# design.net
KiCad netlist of a schematic drawn in Altium Designer
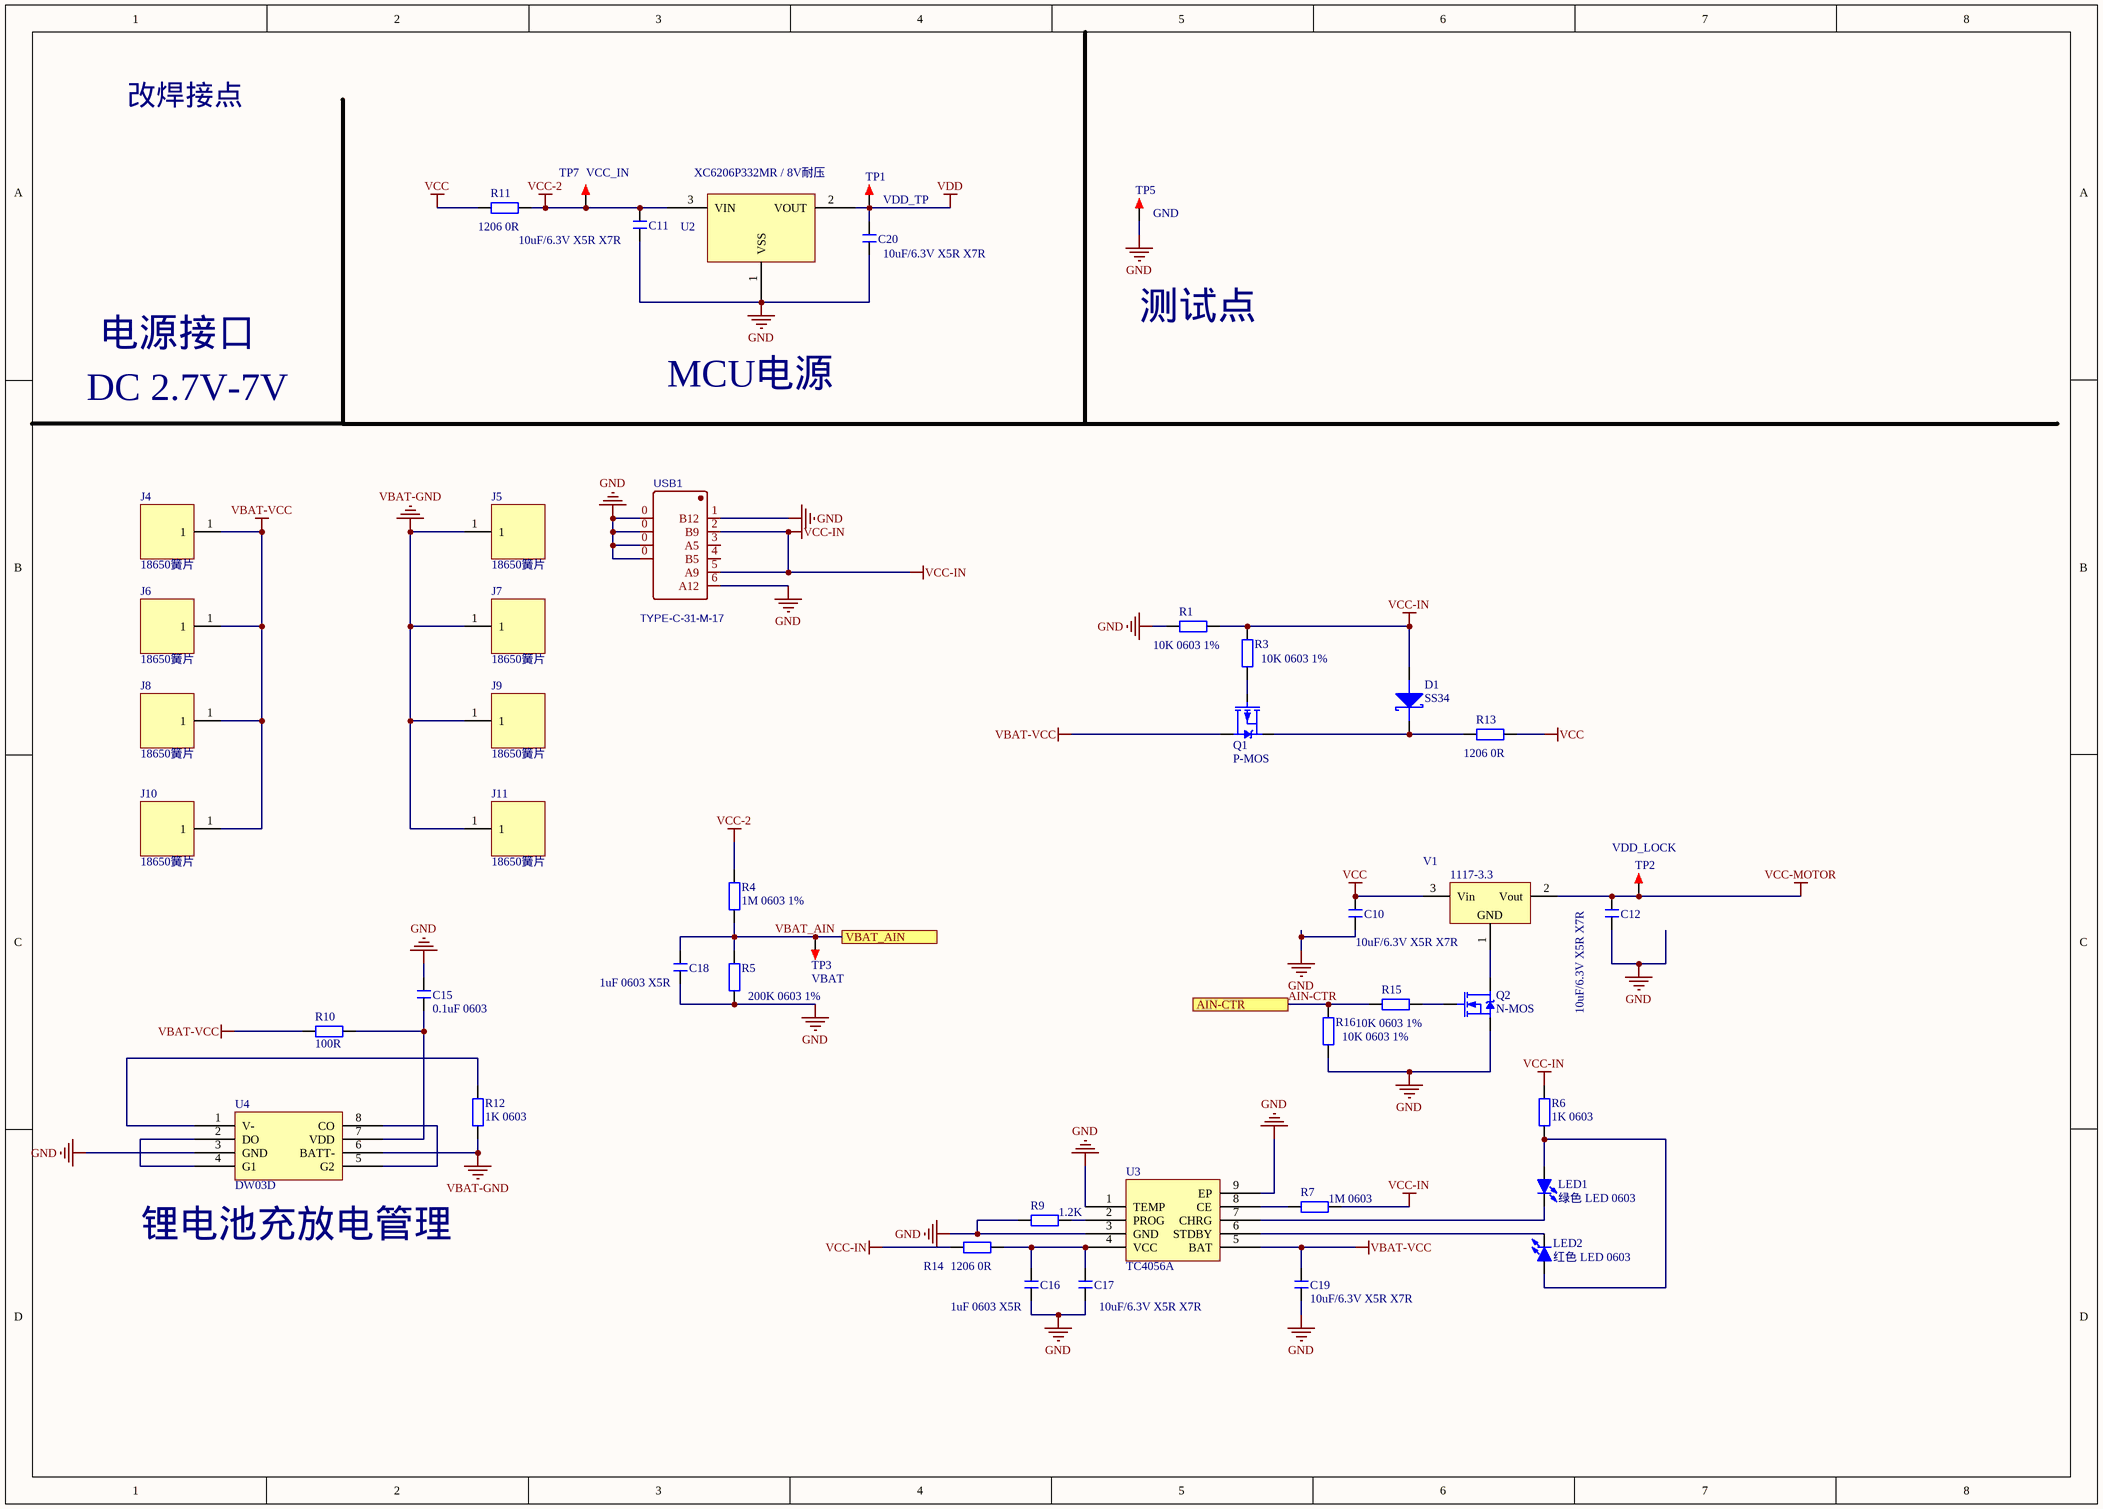
[diagram p0: 电源.SchDoc]

(export (version "E")
  (design (tool "Eeschema 10.0.6"))
  (components
    (comp (ref "C10")
      (value "10uF/6.3V X5R X7R")
      (footprint "C 0603")
      (description "无极性贴片电容")
      (fields (field (name "版权归属") "源创客"))
      (libsource (lib "源创客") (part "C"))
    )
    (comp (ref "C11")
      (value "10uF/6.3V X5R X7R")
      (footprint "C 0603")
      (description "无极性贴片电容")
      (fields (field (name "版权归属") "源创客"))
      (libsource (lib "源创客") (part "C"))
    )
    (comp (ref "C12")
      (value "10uF/6.3V X5R X7R")
      (footprint "C 0603")
      (description "无极性贴片电容")
      (fields (field (name "版权归属") "源创客"))
      (libsource (lib "源创客") (part "C"))
    )
    (comp (ref "C15")
      (value "0.1uF 0603")
      (footprint "C 0603")
      (description "无极性贴片电容")
      (fields (field (name "版权归属") "源创客"))
      (libsource (lib "源创客") (part "C"))
    )
    (comp (ref "C16")
      (value "1uF 0603 X5R")
      (footprint "C 0603")
      (description "无极性贴片电容")
      (fields (field (name "版权归属") "源创客"))
      (libsource (lib "源创客") (part "C"))
    )
    (comp (ref "C17")
      (value "10uF/6.3V X5R X7R")
      (footprint "C 0603")
      (description "无极性贴片电容")
      (fields (field (name "版权归属") "源创客"))
      (libsource (lib "源创客") (part "C"))
    )
    (comp (ref "C18")
      (value "1uF 0603 X5R")
      (footprint "C 0603")
      (description "无极性贴片电容")
      (fields (field (name "版权归属") "源创客"))
      (libsource (lib "源创客") (part "C"))
    )
    (comp (ref "C19")
      (value "10uF/6.3V X5R X7R")
      (footprint "C 0603")
      (description "无极性贴片电容")
      (fields (field (name "版权归属") "源创客"))
      (libsource (lib "源创客") (part "C"))
    )
    (comp (ref "C20")
      (value "10uF/6.3V X5R X7R")
      (footprint "C 0603")
      (description "无极性贴片电容")
      (fields (field (name "版权归属") "源创客"))
      (libsource (lib "源创客") (part "C"))
    )
    (comp (ref "D1")
      (value "SS34")
      (footprint "SMA/DO-214AC")
      (description "肖特基二极管")
      (libsource (lib "二极管") (part "DIODE SCHOTTKY"))
    )
    (comp (ref "J4") (value "18650簧片") (footprint "18650电池簧片") (libsource (lib "") (part "18650簧片_1")))
    (comp (ref "J5") (value "18650簧片") (footprint "18650电池簧片") (libsource (lib "this") (part "18650簧片")))
    (comp (ref "J6") (value "18650簧片") (footprint "18650电池簧片") (libsource (lib "") (part "18650簧片_1")))
    (comp (ref "J7") (value "18650簧片") (footprint "18650电池簧片") (libsource (lib "this") (part "18650簧片")))
    (comp (ref "J8") (value "18650簧片") (footprint "18650电池簧片") (libsource (lib "") (part "18650簧片_1")))
    (comp (ref "J9") (value "18650簧片") (footprint "18650电池簧片") (libsource (lib "this") (part "18650簧片")))
    (comp (ref "J10") (value "18650簧片") (footprint "18650电池簧片") (libsource (lib "") (part "18650簧片_1")))
    (comp (ref "J11") (value "18650簧片") (footprint "18650电池簧片") (libsource (lib "this") (part "18650簧片")))
    (comp (ref "LED1")
      (value "绿色 LED 0603")
      (footprint "LED 0603G")
      (description "贴片LED")
      (fields (field (name "版权归属") "源创客"))
      (libsource (lib "源创客") (part "LED-SMD"))
    )
    (comp (ref "LED2")
      (value "红色 LED 0603")
      (footprint "LED 0603G")
      (description "贴片LED")
      (fields (field (name "版权归属") "源创客"))
      (libsource (lib "源创客") (part "LED-SMD"))
    )
    (comp (ref "Q1")
      (value "P-MOS")
      (footprint "SOT23")
      (description "P沟道场效应管")
      (libsource (lib "MOS管") (part "P-MOS"))
    )
    (comp (ref "Q2")
      (value "N-MOS")
      (footprint "SOT23")
      (description "N沟道场效应管")
      (libsource (lib "MOS管") (part "N-MOS"))
    )
    (comp (ref "R1")
      (value "10K 0603 1%")
      (footprint "R 0603")
      (description "贴片电阻")
      (fields (field (name "版权归属") "源创客"))
      (libsource (lib "源创客") (part "R"))
    )
    (comp (ref "R3")
      (value "10K 0603 1%")
      (footprint "R 0603")
      (description "贴片电阻")
      (fields (field (name "版权归属") "源创客"))
      (libsource (lib "源创客") (part "R"))
    )
    (comp (ref "R4")
      (value "1M 0603 1%")
      (footprint "R 0603")
      (description "贴片电阻")
      (fields (field (name "版权归属") "源创客"))
      (libsource (lib "源创客") (part "R"))
    )
    (comp (ref "R5")
      (value "200K 0603 1%")
      (footprint "R 0603")
      (description "贴片电阻")
      (fields (field (name "版权归属") "源创客"))
      (libsource (lib "源创客") (part "R"))
    )
    (comp (ref "R6")
      (value "1K 0603")
      (footprint "R 0603")
      (description "贴片电阻")
      (fields (field (name "版权归属") "源创客"))
      (libsource (lib "源创客") (part "R"))
    )
    (comp (ref "R7")
      (value "1M 0603")
      (footprint "R 0603")
      (description "贴片电阻")
      (fields (field (name "版权归属") "源创客"))
      (libsource (lib "源创客") (part "R"))
    )
    (comp (ref "R9")
      (value "1.2K")
      (footprint "R 0603")
      (description "贴片电阻")
      (fields (field (name "版权归属") "源创客"))
      (libsource (lib "源创客") (part "R"))
    )
    (comp (ref "R10")
      (value "100R")
      (footprint "R 0603")
      (description "贴片电阻")
      (fields (field (name "版权归属") "源创客"))
      (libsource (lib "源创客") (part "R"))
    )
    (comp (ref "R11")
      (value "1206 0R")
      (footprint "R 1206")
      (description "贴片电阻")
      (fields (field (name "版权归属") "源创客"))
      (libsource (lib "源创客") (part "R"))
    )
    (comp (ref "R12")
      (value "1K 0603")
      (footprint "R 0603")
      (description "贴片电阻")
      (fields (field (name "版权归属") "源创客"))
      (libsource (lib "源创客") (part "R"))
    )
    (comp (ref "R13")
      (value "1206 0R")
      (footprint "R 1206")
      (description "贴片电阻")
      (fields (field (name "版权归属") "源创客"))
      (libsource (lib "源创客") (part "R"))
    )
    (comp (ref "R14")
      (value "1206 0R")
      (footprint "R 1206")
      (description "贴片电阻")
      (fields (field (name "版权归属") "源创客"))
      (libsource (lib "源创客") (part "R"))
    )
    (comp (ref "R15")
      (value "10K 0603 1%")
      (footprint "R 0603")
      (description "贴片电阻")
      (fields (field (name "版权归属") "源创客"))
      (libsource (lib "源创客") (part "R"))
    )
    (comp (ref "R16")
      (value "10K 0603 1%")
      (footprint "R 0603")
      (description "贴片电阻")
      (fields (field (name "版权归属") "源创客"))
      (libsource (lib "源创客") (part "R"))
    )
    (comp (ref "TP1")
      (value "VDD_TP")
      (footprint "TEST 1")
      (description "测试环")
      (fields (field (name "版权归属") "源创客"))
      (libsource (lib "源创客") (part "TEST TP"))
    )
    (comp (ref "TP2")
      (value "VDD_LOCK")
      (footprint "TEST 1")
      (description "测试环")
      (fields (field (name "版权归属") "源创客"))
      (libsource (lib "源创客") (part "TEST TP"))
    )
    (comp (ref "TP3")
      (value "VBAT")
      (footprint "TEST 1")
      (description "测试环")
      (fields (field (name "版权归属") "源创客"))
      (libsource (lib "源创客") (part "TEST TP"))
    )
    (comp (ref "TP5")
      (value "GND")
      (footprint "TEST 1")
      (description "测试环")
      (fields (field (name "版权归属") "源创客"))
      (libsource (lib "源创客") (part "TEST TP"))
    )
    (comp (ref "TP7")
      (value "VCC_IN")
      (footprint "TEST 1")
      (description "测试环")
      (fields (field (name "版权归属") "源创客"))
      (libsource (lib "源创客") (part "TEST TP"))
    )
    (comp (ref "U2")
      (value "XC6206P332MR / 8V耐压")
      (footprint "SOT23-3")
      (description "LDO")
      (libsource (lib "this") (part "XC6206P252MR"))
    )
    (comp (ref "U3")
      (value "TC4056A")
      (footprint "SOP-8_L4.9-W3.9-P1.27-LS6.0-BL-EP")
      (description "锂电池充电IC")
      (libsource (lib "this") (part "TC4056A"))
    )
    (comp (ref "U4")
      (value "DW03D")
      (footprint "TSSOP-8_L4.4-W3.0-P0.65-LS6.4-BL")
      (description "充电保护IC")
      (libsource (lib "this") (part "DW03D"))
    )
    (comp (ref "USB1")
      (value "TYPE-C-31-M-17")
      (footprint "USB-TYPE-C-SMD6")
      (libsource (lib "type-c-sch") (part "TYPE-C-31-M-17"))
    )
    (comp (ref "V1")
      (value "1117-3.3")
      (footprint "SOT223_L")
      (description "三端稳压芯片")
      (fields (field (name "版权归属") "源创客"))
      (libsource (lib "源创客") (part "AMS1117"))
    )
  )
  (nets
    (net (code "1") (name "/AIN-CTR") (class "Default")
      (node (ref "R15") (pin "2") (pinfunction "2_2") (pintype "passive"))
      (node (ref "R16") (pin "1") (pinfunction "1_1") (pintype "passive"))
    )
    (net (code "2") (name "/VBAT_AIN") (class "Default")
      (node (ref "C18") (pin "2") (pinfunction "2_2") (pintype "passive"))
      (node (ref "R4") (pin "2") (pinfunction "2_2") (pintype "passive"))
      (node (ref "R5") (pin "2") (pinfunction "2_2") (pintype "passive"))
      (node (ref "TP3") (pin "1") (pinfunction "1_1") (pintype "passive"))
    )
    (net (code "3") (name "GND") (class "Default")
      (node (ref "C10") (pin "1") (pinfunction "1_1") (pintype "passive"))
      (node (ref "C11") (pin "1") (pinfunction "1_1") (pintype "passive"))
      (node (ref "C12") (pin "1") (pinfunction "1_1") (pintype "passive"))
      (node (ref "C15") (pin "2") (pinfunction "2_2") (pintype "passive"))
      (node (ref "C16") (pin "2") (pinfunction "2_2") (pintype "passive"))
      (node (ref "C17") (pin "2") (pinfunction "2_2") (pintype "passive"))
      (node (ref "C18") (pin "1") (pinfunction "1_1") (pintype "passive"))
      (node (ref "C19") (pin "2") (pinfunction "2_2") (pintype "passive"))
      (node (ref "C20") (pin "1") (pinfunction "1_1") (pintype "passive"))
      (node (ref "Q2") (pin "S") (pinfunction "S_S") (pintype "passive"))
      (node (ref "R1") (pin "2") (pinfunction "2_2") (pintype "passive"))
      (node (ref "R16") (pin "2") (pinfunction "2_2") (pintype "passive"))
      (node (ref "R5") (pin "1") (pinfunction "1_1") (pintype "passive"))
      (node (ref "R9") (pin "2") (pinfunction "2_2") (pintype "passive"))
      (node (ref "TP5") (pin "1") (pinfunction "1_1") (pintype "passive"))
      (node (ref "U2") (pin "1") (pinfunction "VSS_1") (pintype "passive"))
      (node (ref "U3") (pin "1") (pinfunction "TEMP_1") (pintype "passive"))
      (node (ref "U3") (pin "3") (pinfunction "GND_3") (pintype "passive"))
      (node (ref "U3") (pin "9") (pinfunction "EP_9") (pintype "passive"))
      (node (ref "U4") (pin "3") (pinfunction "GND_3") (pintype "passive"))
      (node (ref "USB1") (pin "0") (pinfunction "0_0") (pintype "passive"))
      (node (ref "USB1") (pin "1") (pinfunction "B12_1") (pintype "passive"))
      (node (ref "USB1") (pin "6") (pinfunction "A12_6") (pintype "passive"))
    )
    (net (code "4") (name "Net-(D1-PadK)") (class "Default")
      (node (ref "D1") (pin "K") (pinfunction "K_K") (pintype "passive"))
      (node (ref "Q1") (pin "S") (pinfunction "S_S") (pintype "passive"))
      (node (ref "R13") (pin "1") (pinfunction "1_1") (pintype "passive"))
    )
    (net (code "5") (name "Net-(LED1-A)") (class "Default")
      (node (ref "LED1") (pin "1") (pinfunction "A_1") (pintype "passive"))
      (node (ref "LED2") (pin "1") (pinfunction "A_1") (pintype "passive"))
      (node (ref "R6") (pin "2") (pinfunction "2_2") (pintype "passive"))
    )
    (net (code "6") (name "Net-(LED1-K)") (class "Default")
      (node (ref "LED1") (pin "2") (pinfunction "K_2") (pintype "passive"))
      (node (ref "U3") (pin "7") (pinfunction "CHRG_7") (pintype "passive"))
    )
    (net (code "7") (name "Net-(LED2-K)") (class "Default")
      (node (ref "LED2") (pin "2") (pinfunction "K_2") (pintype "passive"))
      (node (ref "U3") (pin "6") (pinfunction "STDBY_6") (pintype "passive"))
    )
    (net (code "8") (name "Net-(Q1-PadG)") (class "Default")
      (node (ref "Q1") (pin "G") (pinfunction "G_G") (pintype "passive"))
      (node (ref "R3") (pin "2") (pinfunction "2_2") (pintype "passive"))
    )
    (net (code "9") (name "Net-(Q2-PadG)") (class "Default")
      (node (ref "Q2") (pin "G") (pinfunction "G_G") (pintype "passive"))
      (node (ref "R15") (pin "1") (pinfunction "1_1") (pintype "passive"))
    )
    (net (code "10") (name "Net-(U3-CE)") (class "Default")
      (node (ref "R7") (pin "2") (pinfunction "2_2") (pintype "passive"))
      (node (ref "U3") (pin "8") (pinfunction "CE_8") (pintype "passive"))
    )
    (net (code "11") (name "Net-(U3-PROG)") (class "Default")
      (node (ref "R9") (pin "1") (pinfunction "1_1") (pintype "passive"))
      (node (ref "U3") (pin "2") (pinfunction "PROG_2") (pintype "passive"))
    )
    (net (code "12") (name "Net-(U3-VCC)") (class "Default")
      (node (ref "C16") (pin "1") (pinfunction "1_1") (pintype "passive"))
      (node (ref "C17") (pin "1") (pinfunction "1_1") (pintype "passive"))
      (node (ref "R14") (pin "2") (pinfunction "2_2") (pintype "passive"))
      (node (ref "U3") (pin "4") (pinfunction "VCC_4") (pintype "passive"))
    )
    (net (code "13") (name "Net-(U4-CO)") (class "Default")
      (node (ref "U4") (pin "5") (pinfunction "G2_5") (pintype "passive"))
      (node (ref "U4") (pin "8") (pinfunction "CO_8") (pintype "passive"))
    )
    (net (code "14") (name "Net-(U4-DO)") (class "Default")
      (node (ref "U4") (pin "2") (pinfunction "DO_2") (pintype "passive"))
      (node (ref "U4") (pin "4") (pinfunction "G1_4") (pintype "passive"))
    )
    (net (code "15") (name "Net-(U4-V-)") (class "Default")
      (node (ref "R12") (pin "2") (pinfunction "2_2") (pintype "passive"))
      (node (ref "U4") (pin "1") (pinfunction "V-_1") (pintype "passive"))
    )
    (net (code "16") (name "Net-(U4-VDD)") (class "Default")
      (node (ref "C15") (pin "1") (pinfunction "1_1") (pintype "passive"))
      (node (ref "R10") (pin "1") (pinfunction "1_1") (pintype "passive"))
      (node (ref "U4") (pin "7") (pinfunction "VDD_7") (pintype "passive"))
    )
    (net (code "17") (name "Net-(V1-GND)") (class "Default")
      (node (ref "Q2") (pin "D") (pinfunction "D_D") (pintype "passive"))
      (node (ref "V1") (pin "1") (pinfunction "GND_1") (pintype "passive"))
    )
    (net (code "18") (name "VBAT-GND") (class "Default")
      (node (ref "J11") (pin "1") (pinfunction "1_1") (pintype "passive"))
      (node (ref "J5") (pin "1") (pinfunction "1_1") (pintype "passive"))
      (node (ref "J7") (pin "1") (pinfunction "1_1") (pintype "passive"))
      (node (ref "J9") (pin "1") (pinfunction "1_1") (pintype "passive"))
      (node (ref "R12") (pin "1") (pinfunction "1_1") (pintype "passive"))
      (node (ref "U4") (pin "6") (pinfunction "BATT-_6") (pintype "passive"))
    )
    (net (code "19") (name "VBAT-VCC") (class "Default")
      (node (ref "C19") (pin "1") (pinfunction "1_1") (pintype "passive"))
      (node (ref "J10") (pin "1") (pinfunction "1_1") (pintype "passive"))
      (node (ref "J4") (pin "1") (pinfunction "1_1") (pintype "passive"))
      (node (ref "J6") (pin "1") (pinfunction "1_1") (pintype "passive"))
      (node (ref "J8") (pin "1") (pinfunction "1_1") (pintype "passive"))
      (node (ref "Q1") (pin "D") (pinfunction "D_D") (pintype "passive"))
      (node (ref "R10") (pin "2") (pinfunction "2_2") (pintype "passive"))
      (node (ref "U3") (pin "5") (pinfunction "BAT_5") (pintype "passive"))
    )
    (net (code "20") (name "VCC") (class "Default")
      (node (ref "C10") (pin "2") (pinfunction "2_2") (pintype "passive"))
      (node (ref "R11") (pin "1") (pinfunction "1_1") (pintype "passive"))
      (node (ref "R13") (pin "2") (pinfunction "2_2") (pintype "passive"))
      (node (ref "V1") (pin "3") (pinfunction "Vin_3") (pintype "passive"))
    )
    (net (code "21") (name "VCC-2") (class "Default")
      (node (ref "C11") (pin "2") (pinfunction "2_2") (pintype "passive"))
      (node (ref "R11") (pin "2") (pinfunction "2_2") (pintype "passive"))
      (node (ref "R4") (pin "1") (pinfunction "1_1") (pintype "passive"))
      (node (ref "TP7") (pin "1") (pinfunction "1_1") (pintype "passive"))
      (node (ref "U2") (pin "3") (pinfunction "VIN_3") (pintype "passive"))
    )
    (net (code "22") (name "VCC-IN") (class "Default")
      (node (ref "D1") (pin "A") (pinfunction "A_A") (pintype "passive"))
      (node (ref "R1") (pin "1") (pinfunction "1_1") (pintype "passive"))
      (node (ref "R14") (pin "1") (pinfunction "1_1") (pintype "passive"))
      (node (ref "R3") (pin "1") (pinfunction "1_1") (pintype "passive"))
      (node (ref "R6") (pin "1") (pinfunction "1_1") (pintype "passive"))
      (node (ref "R7") (pin "1") (pinfunction "1_1") (pintype "passive"))
      (node (ref "USB1") (pin "2") (pinfunction "B9_2") (pintype "passive"))
      (node (ref "USB1") (pin "5") (pinfunction "A9_5") (pintype "passive"))
    )
    (net (code "23") (name "VCC-MOTOR") (class "Default")
      (node (ref "C12") (pin "2") (pinfunction "2_2") (pintype "passive"))
      (node (ref "TP2") (pin "1") (pinfunction "1_1") (pintype "passive"))
      (node (ref "V1") (pin "2") (pinfunction "Vout_2") (pintype "passive"))
    )
    (net (code "24") (name "VDD") (class "Default")
      (node (ref "C20") (pin "2") (pinfunction "2_2") (pintype "passive"))
      (node (ref "TP1") (pin "1") (pinfunction "1_1") (pintype "passive"))
      (node (ref "U2") (pin "2") (pinfunction "VOUT_2") (pintype "passive"))
    )
    (net (code "25") (name "unconnected-(USB1-A5-Pad3)") (class "Default")
      (node (ref "USB1") (pin "3") (pinfunction "A5_3") (pintype "passive"))
    )
    (net (code "26") (name "unconnected-(USB1-B5-Pad4)") (class "Default")
      (node (ref "USB1") (pin "4") (pinfunction "B5_4") (pintype "passive"))
    )
  )
)
